# Out2.net
KiCad netlist of a schematic drawn in Altium Designer
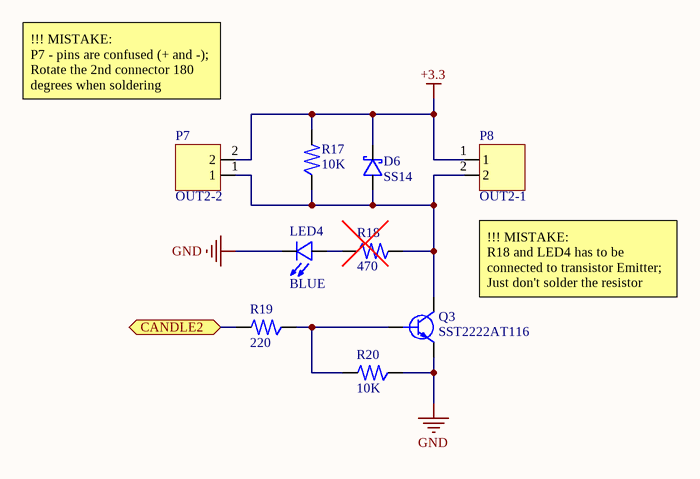
[diagram p0: Out2.SchDoc]

(export (version "E")
  (design (tool "Eeschema 10.0.6"))
  (components
    (comp (ref "D6")
      (value "SS14")
      (footprint "SMT_DIODE_SCHTKY_VISHAI")
      (description "SMT Diode Schottky Vishay DO-214AC SS14-M3/5AT IF=1A VR=40 V FV=0.5VG")
      (libsource (lib "SMT_DIODE_SCHTKY_VISHAI") (part "SMT_DIODE_SCHTKY_VISHAI"))
    )
    (comp (ref "LED4")
      (value "BLUE")
      (footprint "SMT_LED_0805(2012)_WURTH")
      (description "LED 0805(2012) 20mA 2V 150080YS75000 by Wurth Elektronik")
      (libsource (lib "SMT_LED_0805(2012)_WURTH") (part "SMT_LED_0805(2012)_WURTH"))
    )
    (comp (ref "P7")
      (value "OUT2-2")
      (footprint "THT_CON_WAFER_2P_NEL_2217S-02-WH2")
      (description "Connector Wafer NELTRON 2-Pins Pitch-2.54mm 250V/3A 2217S-02-WH2")
      (libsource (lib "") (part "THT_CON_WAFER_2P_NEL_2217S-02-WH2_1"))
    )
    (comp (ref "P8")
      (value "OUT2-1")
      (footprint "THT_CON_WAFER_2P_NEL_2217S-02-WH2")
      (description "Connector Wafer NELTRON 2-Pins Pitch-2.54mm 250V/3A 2217S-02-WH2")
      (libsource (lib "THT_CON_WAFER_2P_NEL_2217S-02-WH2") (part "THT_CON_WAFER_2P_NEL_2217S-02-WH2"))
    )
    (comp (ref "Q3")
      (value "SST2222AT116")
      (footprint "SMT_TRANS_SST2222AT116_SOT23")
      (description "Transistor NPN SST2222AT116 SOT23 700mA 40V")
      (libsource (lib "SMT_TRANS_SST2222AT116_SOT23") (part "SMT_TRANS_SST2222AT116_SOT23"))
    )
    (comp (ref "R17")
      (value "10K")
      (footprint "SMT_RES_0805(2012)")
      (description "0805(2012) Resistor 1/4-1/8W 150V 2A")
      (libsource (lib "SMT_RES_0805(2012)") (part "SMT_RES_0805(2012)"))
    )
    (comp (ref "R18")
      (value "470")
      (footprint "SMT_RES_0805(2012)")
      (description "0805(2012) Resistor 1/4-1/8W 150V 2A")
      (libsource (lib "SMT_RES_0805(2012)") (part "SMT_RES_0805(2012)"))
    )
    (comp (ref "R19")
      (value "220")
      (footprint "SMT_RES_0805(2012)")
      (description "0805(2012) Resistor 1/4-1/8W 150V 2A")
      (libsource (lib "SMT_RES_0805(2012)") (part "SMT_RES_0805(2012)"))
    )
    (comp (ref "R20")
      (value "10K")
      (footprint "SMT_RES_0805(2012)")
      (description "0805(2012) Resistor 1/4-1/8W 150V 2A")
      (libsource (lib "SMT_RES_0805(2012)") (part "SMT_RES_0805(2012)"))
    )
  )
  (nets
    (net (code "1") (name "+3.3") (class "Default")
      (node (ref "D6") (pin "2") (pinfunction "2_2") (pintype "passive"))
      (node (ref "P7") (pin "2") (pinfunction "2_2") (pintype "passive"))
      (node (ref "P8") (pin "1") (pinfunction "1_1") (pintype "passive"))
      (node (ref "R17") (pin "1") (pinfunction "1_1") (pintype "passive"))
    )
    (net (code "2") (name "/CANDLE2") (class "Default")
      (node (ref "R19") (pin "1") (pinfunction "1_1") (pintype "passive"))
    )
    (net (code "3") (name "GND") (class "Default")
      (node (ref "LED4") (pin "1") (pinfunction "1_1") (pintype "passive"))
      (node (ref "Q3") (pin "1") (pinfunction "E_1") (pintype "passive"))
      (node (ref "R20") (pin "2") (pinfunction "2_2") (pintype "passive"))
    )
    (net (code "4") (name "Net-(LED4-Pad2)") (class "Default")
      (node (ref "LED4") (pin "2") (pinfunction "2_2") (pintype "passive"))
      (node (ref "R18") (pin "2") (pinfunction "2_2") (pintype "passive"))
    )
    (net (code "5") (name "Net-(Q3-B)") (class "Default")
      (node (ref "Q3") (pin "2") (pinfunction "B_2") (pintype "passive"))
      (node (ref "R19") (pin "2") (pinfunction "2_2") (pintype "passive"))
      (node (ref "R20") (pin "1") (pinfunction "1_1") (pintype "passive"))
    )
    (net (code "6") (name "Net-(Q3-C)") (class "Default")
      (node (ref "D6") (pin "1") (pinfunction "1_1") (pintype "passive"))
      (node (ref "P7") (pin "1") (pinfunction "1_1") (pintype "passive"))
      (node (ref "P8") (pin "2") (pinfunction "2_2") (pintype "passive"))
      (node (ref "Q3") (pin "3") (pinfunction "C_3") (pintype "passive"))
      (node (ref "R17") (pin "2") (pinfunction "2_2") (pintype "passive"))
      (node (ref "R18") (pin "1") (pinfunction "1_1") (pintype "passive"))
    )
  )
)
